# Carrier_Board.net
KiCad netlist of a schematic drawn in EAGLE
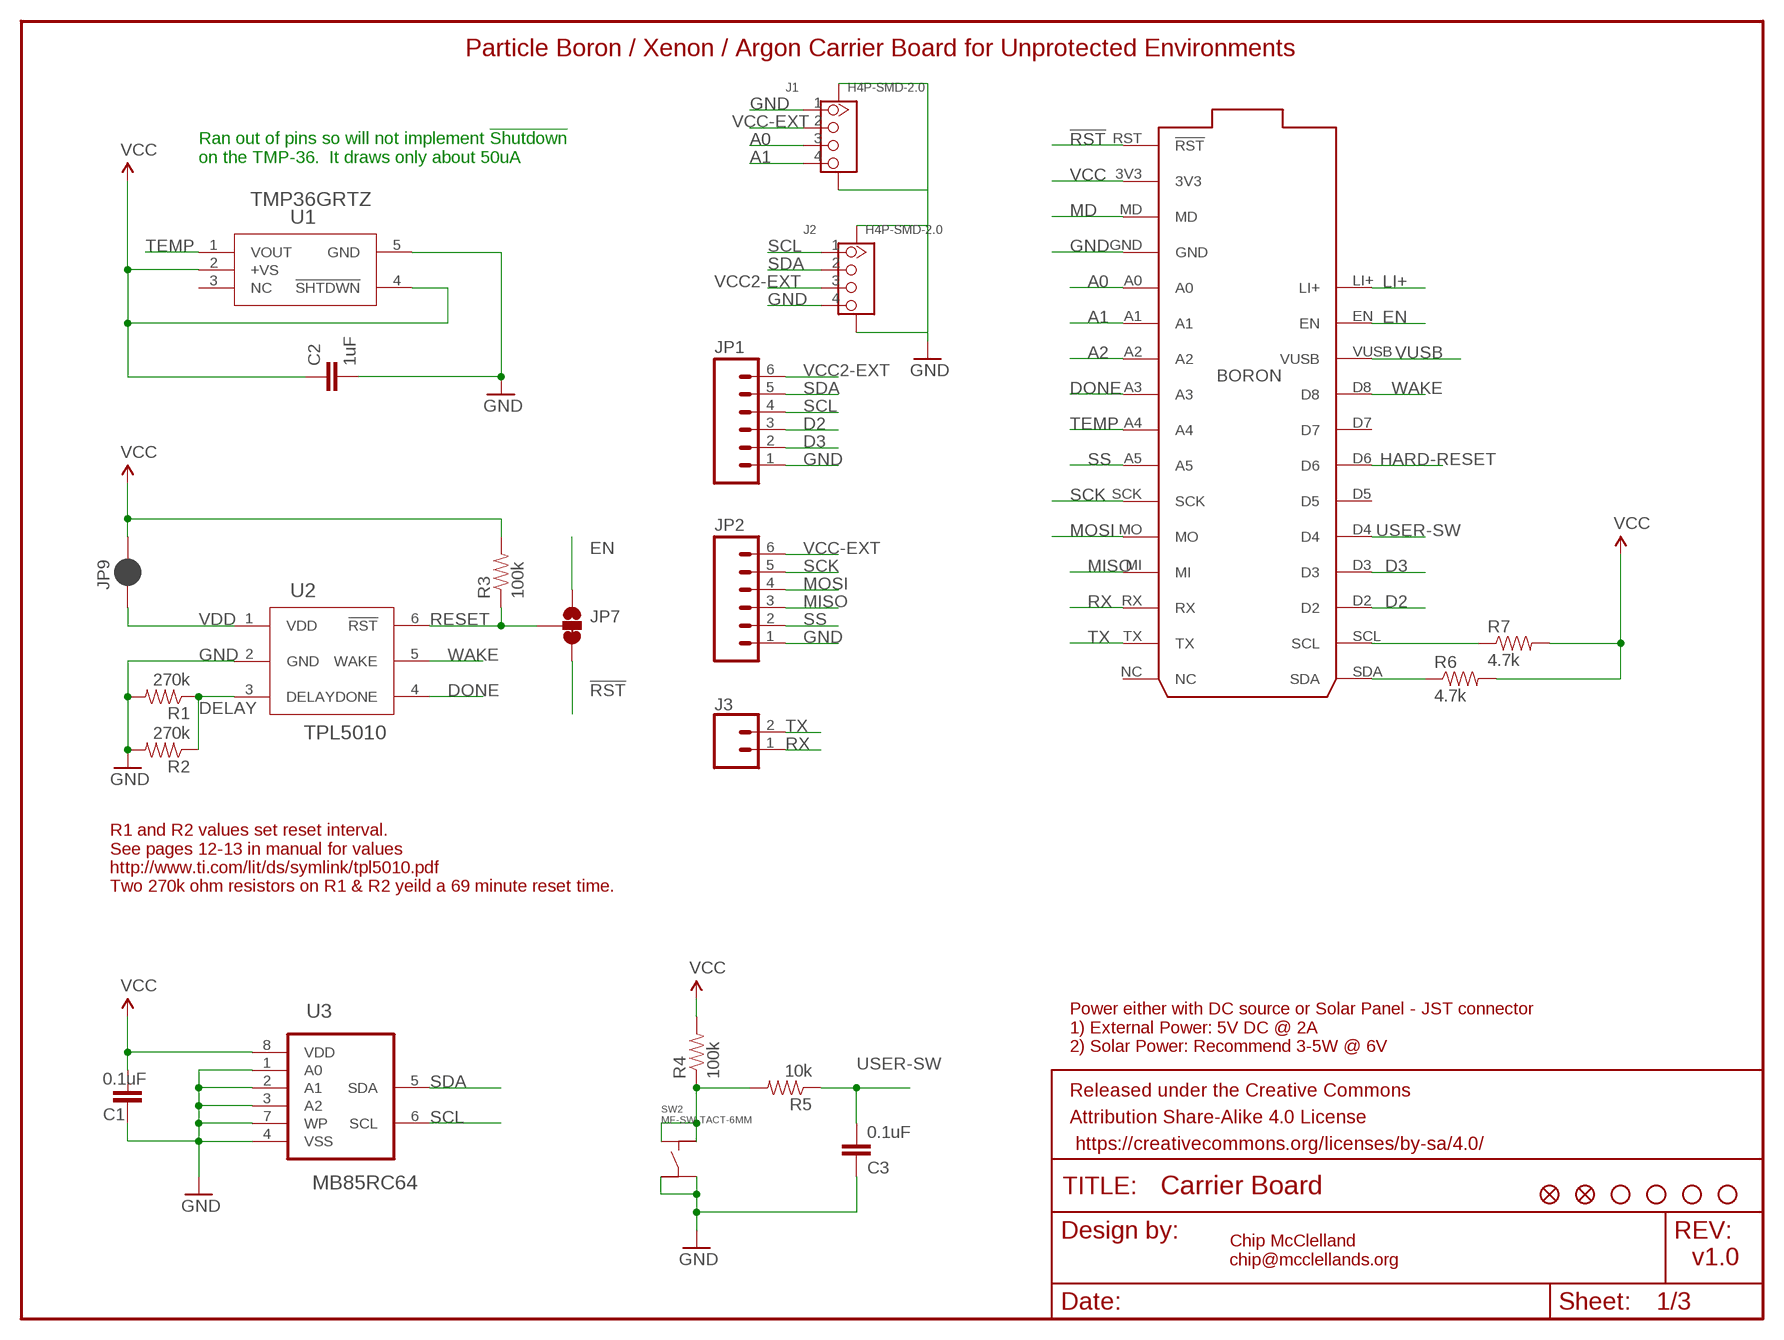
[diagram p0: schematic, sheet 1]
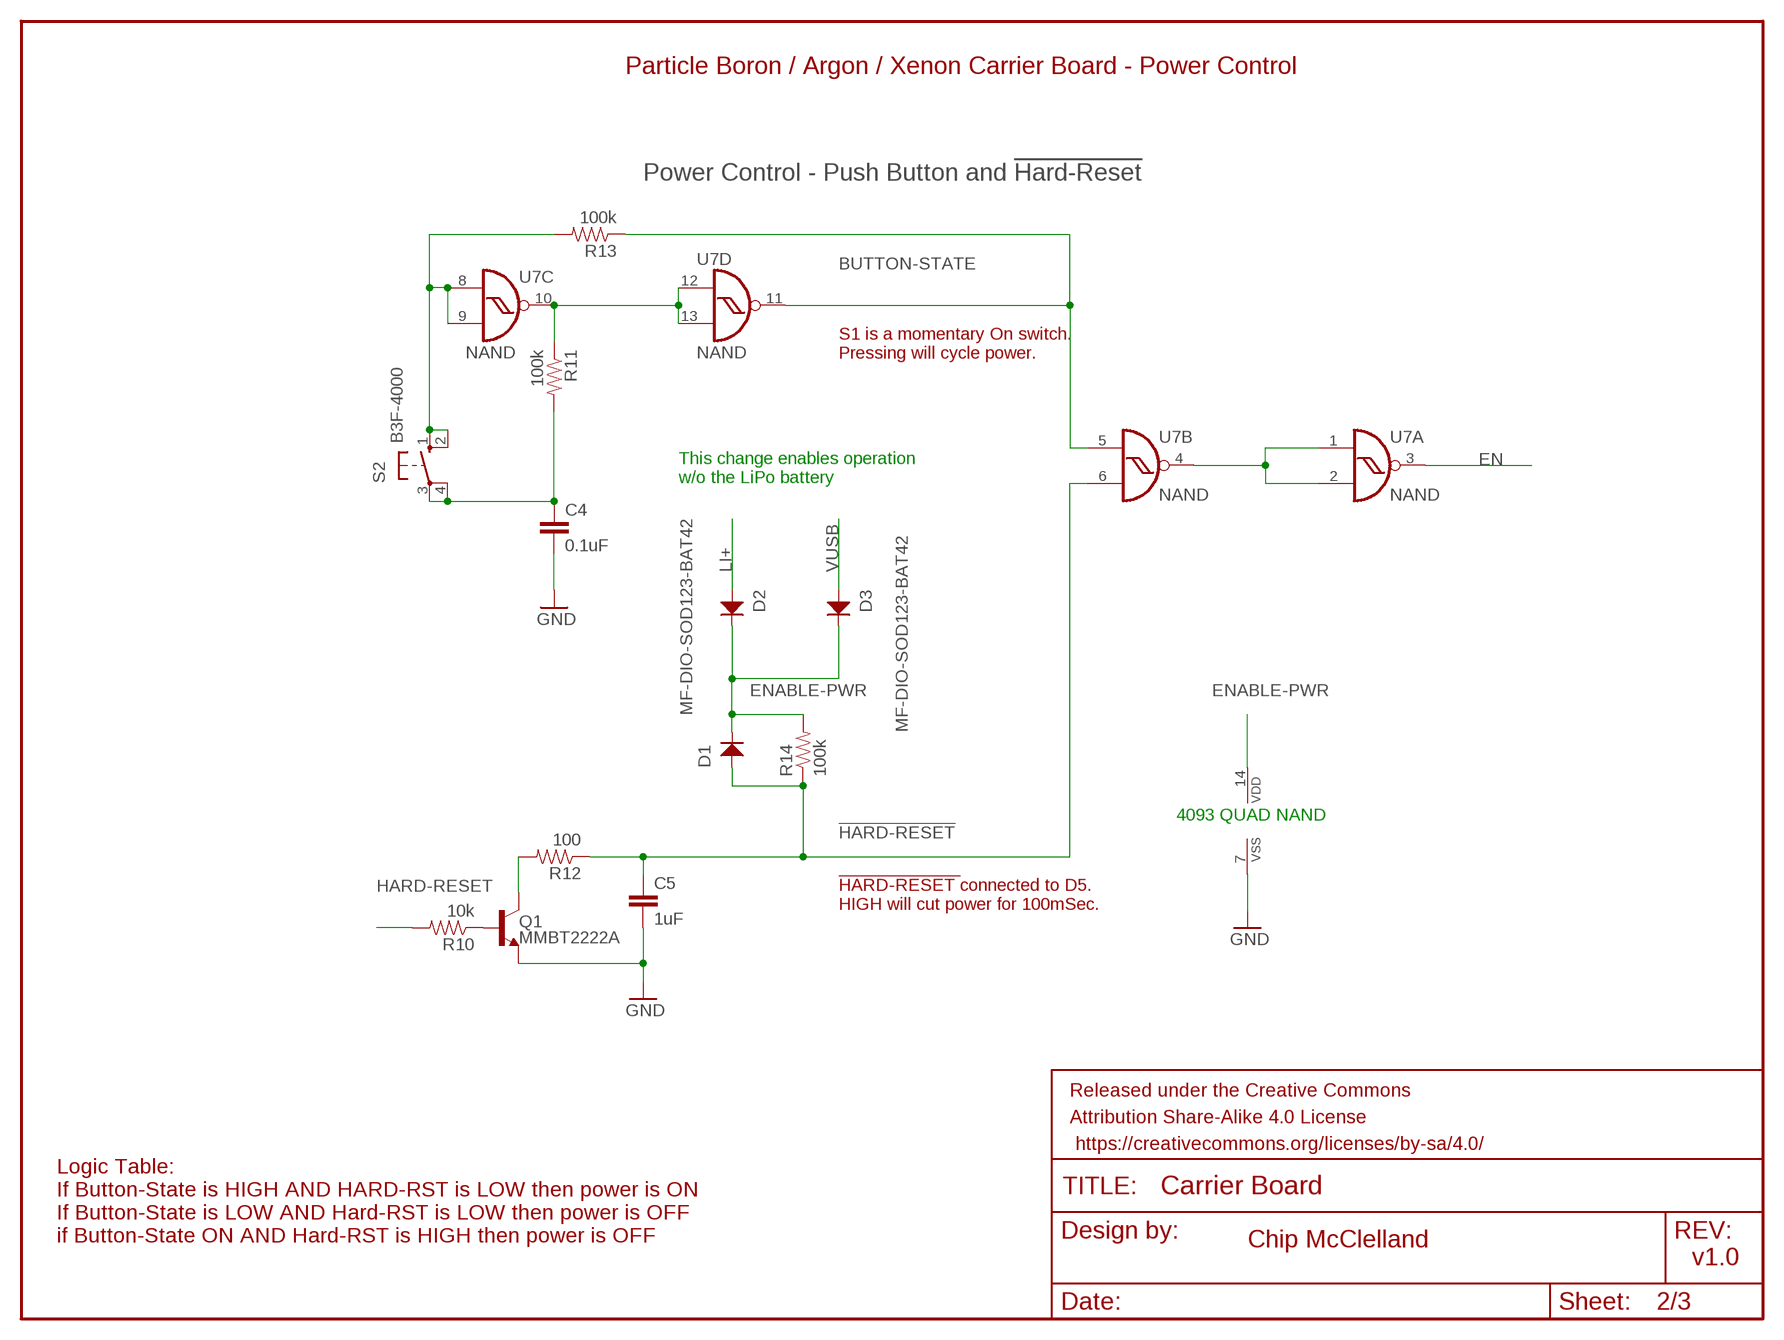
[diagram p1: schematic, sheet 2]
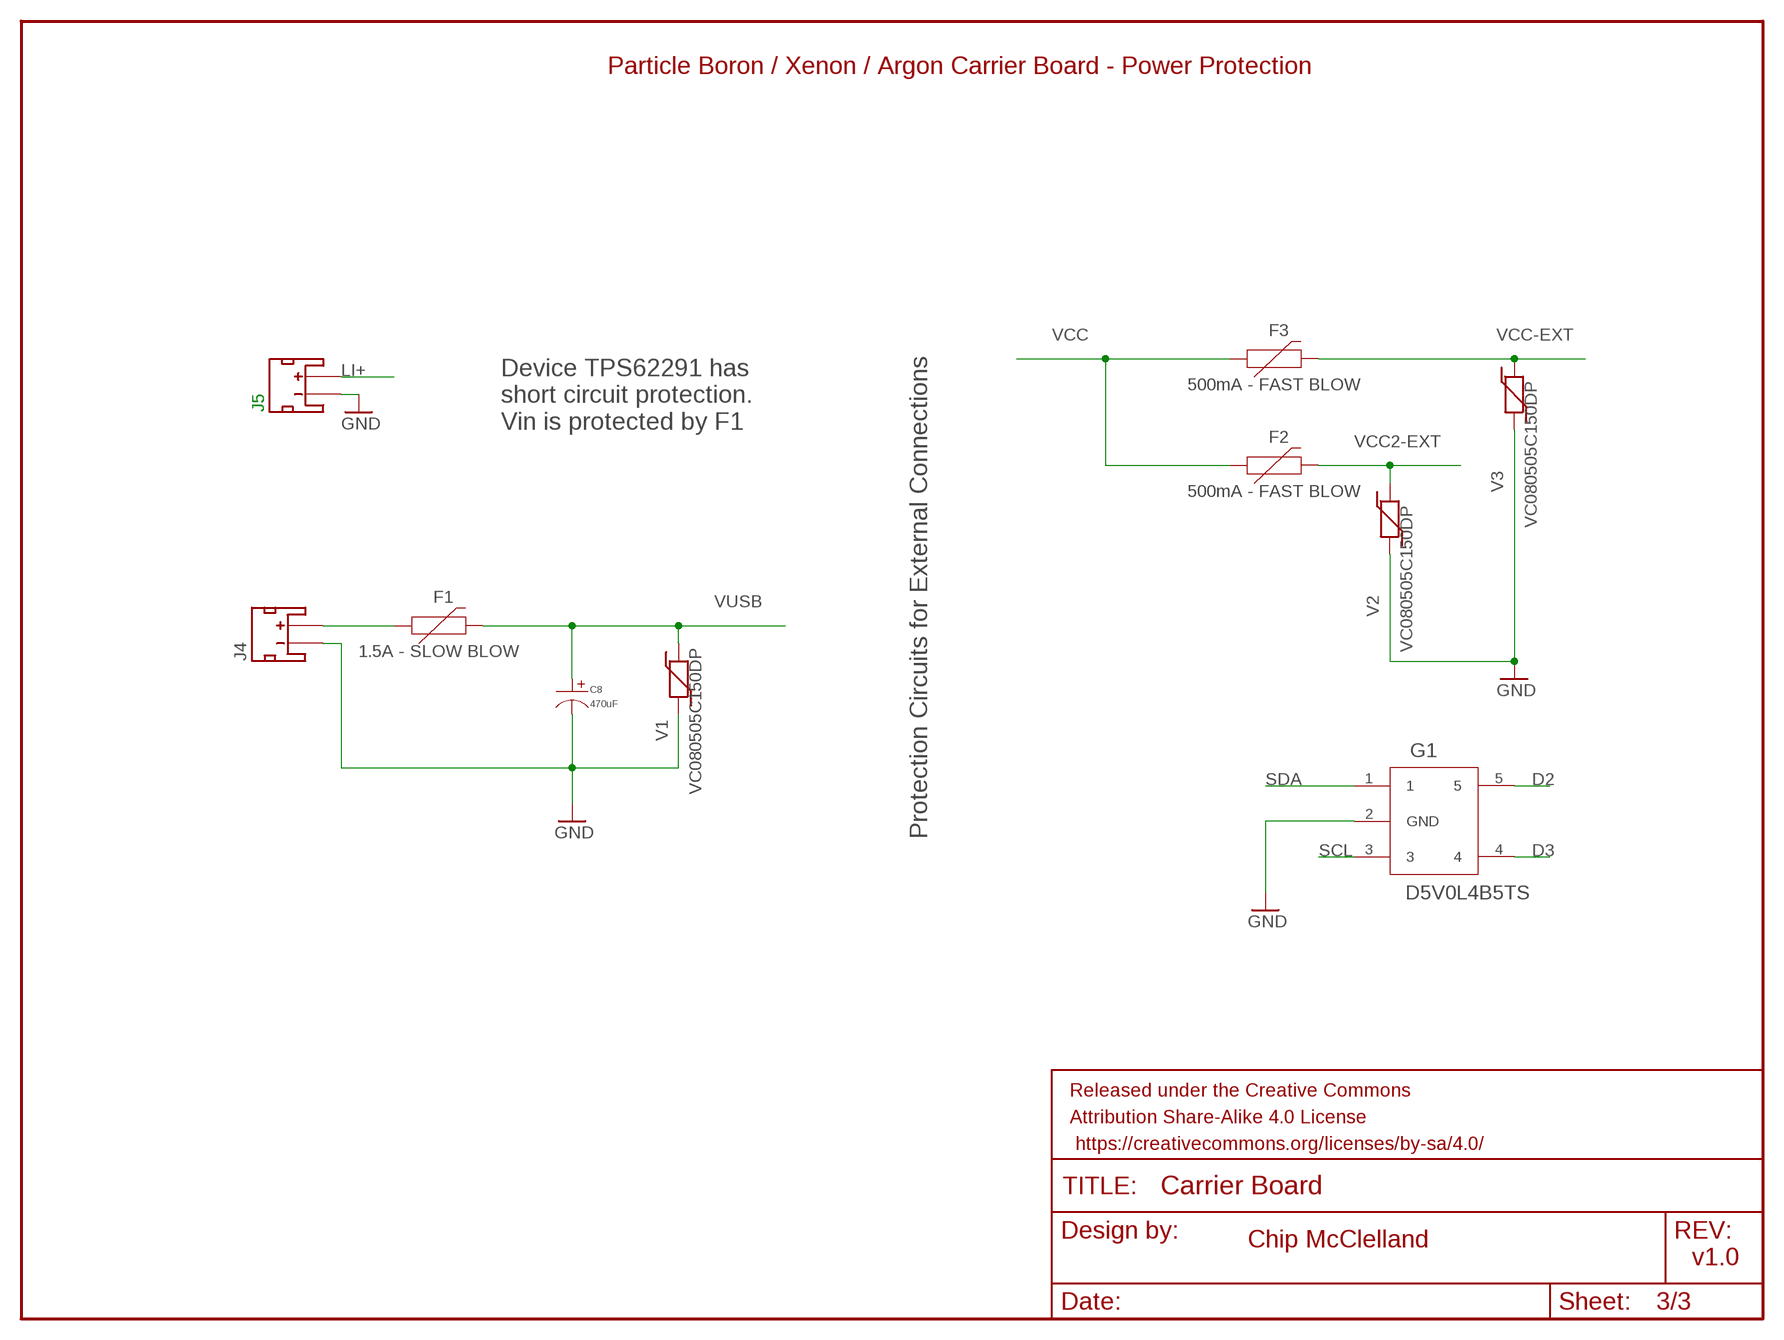
[diagram p2: schematic, sheet 3]

(export (version "E")
  (design (tool "Eeschema 10.0.6"))
  (components
    (comp (ref "C8")
      (value "470uF")
      (footprint "eagle-import:CP10MM")
      (libsource (lib "eagle-import") (part "CAPACITOR_P_10MM"))
    )
    (comp (ref "F1")
      (value "1.5A - SLOW BLOW")
      (footprint "eagle-import:1206")
      (libsource (lib "eagle-import") (part "PPTC_HALF-AMP"))
    )
    (comp (ref "F2")
      (value "500mA - FAST BLOW")
      (footprint "eagle-import:1206")
      (libsource (lib "eagle-import") (part "PPTC_HALF-AMP"))
    )
    (comp (ref "F3")
      (value "500mA - FAST BLOW")
      (footprint "eagle-import:1206")
      (libsource (lib "eagle-import") (part "PPTC_HALF-AMP"))
    )
    (comp (ref "FRAME3")
      (value "FRAME-LETTER")
      (footprint "eagle-import:CREATIVE_COMMONS")
      (libsource (lib "eagle-import") (part "FRAME-LETTER"))
    )
    (comp (ref "G1")
      (value "D5V0L4B5TS")
      (footprint "eagle-import:SOT-23-5")
      (libsource (lib "eagle-import") (part "D5V0L4B5TS"))
    )
    (comp (ref "J4")
      (value "S2B-PH-SM4-TB(LF)(SN)")
      (footprint "eagle-import:JST-2-SMD")
      (libsource (lib "eagle-import") (part "JST_2MM_MALE"))
    )
    (comp (ref "J5")
      (value "S2B-PH-SM4-TB(LF)(SN)")
      (footprint "eagle-import:JST-2-SMD")
      (libsource (lib "eagle-import") (part "JST_2MM_MALE"))
    )
    (comp (ref "V1")
      (value "VC080505C150DP")
      (footprint "eagle-import:0805")
      (libsource (lib "eagle-import") (part "VARISTOR"))
    )
    (comp (ref "V2")
      (value "VC080505C150DP")
      (footprint "eagle-import:0805")
      (libsource (lib "eagle-import") (part "VARISTOR"))
    )
    (comp (ref "V3")
      (value "VC080505C150DP")
      (footprint "eagle-import:0805")
      (libsource (lib "eagle-import") (part "VARISTOR"))
    )
    (comp (ref "BORON/ARGON/XENON")
      (value "PARTICLE-DEVICES-BORON")
      (footprint "eagle-import:PARTICLE-DEVICES_BORON")
      (libsource (lib "eagle-import") (part "PARTICLE-DEVICES-BORON"))
    )
    (comp (ref "C1")
      (value "0.1uF")
      (footprint "eagle-import:0805@1")
      (libsource (lib "eagle-import") (part "CAP0805"))
    )
    (comp (ref "C2")
      (value "1uF")
      (footprint "eagle-import:0805@1")
      (libsource (lib "eagle-import") (part "CAP0805"))
    )
    (comp (ref "C3")
      (value "0.1uF")
      (footprint "eagle-import:0805@1")
      (libsource (lib "eagle-import") (part "CAP0805"))
    )
    (comp (ref "FD1")
      (value "FIDUCIALUFIDUCIAL")
      (footprint "eagle-import:FIDUCIAL-MICRO")
      (libsource (lib "eagle-import") (part "FIDUCIALUFIDUCIAL"))
    )
    (comp (ref "FD2")
      (value "FIDUCIALUFIDUCIAL")
      (footprint "eagle-import:FIDUCIAL-MICRO")
      (libsource (lib "eagle-import") (part "FIDUCIALUFIDUCIAL"))
    )
    (comp (ref "FRAME1")
      (value "FRAME-LETTER")
      (footprint "eagle-import:CREATIVE_COMMONS")
      (libsource (lib "eagle-import") (part "FRAME-LETTER"))
    )
    (comp (ref "J1")
      (value "H4P-SMD-2.0")
      (footprint "eagle-import:HW4-SMD-2.0")
      (libsource (lib "eagle-import") (part "GROVE-CONNECTOR-SMD(4+2P-2.0)"))
    )
    (comp (ref "J2")
      (value "H4P-SMD-2.0")
      (footprint "eagle-import:HW4-SMD-2.0")
      (libsource (lib "eagle-import") (part "GROVE-CONNECTOR-SMD(4+2P-2.0)"))
    )
    (comp (ref "J3")
      (value "CONN_02")
      (footprint "eagle-import:1X02")
      (libsource (lib "eagle-import") (part "CONN_02"))
    )
    (comp (ref "JP1")
      (value "M06LOCK")
      (footprint "eagle-import:1X06_LOCK")
      (libsource (lib "eagle-import") (part "M06LOCK"))
    )
    (comp (ref "JP2")
      (value "M06LOCK")
      (footprint "eagle-import:1X06_LOCK")
      (libsource (lib "eagle-import") (part "M06LOCK"))
    )
    (comp (ref "JP3")
      (value "STAND-OFF")
      (footprint "eagle-import:STAND-OFF")
      (libsource (lib "eagle-import") (part "STAND-OFF"))
    )
    (comp (ref "JP4")
      (value "STAND-OFF")
      (footprint "eagle-import:STAND-OFF")
      (libsource (lib "eagle-import") (part "STAND-OFF"))
    )
    (comp (ref "JP5")
      (value "STAND-OFF")
      (footprint "eagle-import:STAND-OFF")
      (libsource (lib "eagle-import") (part "STAND-OFF"))
    )
    (comp (ref "JP6")
      (value "STAND-OFF")
      (footprint "eagle-import:STAND-OFF")
      (libsource (lib "eagle-import") (part "STAND-OFF"))
    )
    (comp (ref "JP7")
      (value "JUMPER-SMT_3_1-NC_TRACE_SILK")
      (footprint "eagle-import:SMT-JUMPER_3_1-NC_TRACE_SILK")
      (libsource (lib "eagle-import") (part "JUMPER-SMT_3_1-NC_TRACE_SILK"))
    )
    (comp (ref "JP9")
      (value "JUMPER-SMT_2_NC_PASTE_SILK")
      (footprint "eagle-import:SMT-JUMPER_2_NC_PASTE_SILK")
      (libsource (lib "eagle-import") (part "JUMPER-SMT_2_NC_PASTE_SILK"))
    )
    (comp (ref "R1")
      (value "270k")
      (footprint "eagle-import:0805")
      (libsource (lib "eagle-import") (part "RESISTOR0805-RES"))
    )
    (comp (ref "R2")
      (value "270k")
      (footprint "eagle-import:0805")
      (libsource (lib "eagle-import") (part "RESISTOR0805-RES"))
    )
    (comp (ref "R3")
      (value "100k")
      (footprint "eagle-import:0805")
      (libsource (lib "eagle-import") (part "RESISTOR0805-RES"))
    )
    (comp (ref "R4")
      (value "100k")
      (footprint "eagle-import:0805")
      (libsource (lib "eagle-import") (part "RESISTOR0805-RES"))
    )
    (comp (ref "R5")
      (value "10k")
      (footprint "eagle-import:0805")
      (libsource (lib "eagle-import") (part "RESISTOR0805-RES"))
    )
    (comp (ref "R6")
      (value "4.7k")
      (footprint "eagle-import:0805")
      (libsource (lib "eagle-import") (part "RESISTOR0805-RES"))
    )
    (comp (ref "R7")
      (value "4.7k")
      (footprint "eagle-import:0805")
      (libsource (lib "eagle-import") (part "RESISTOR0805-RES"))
    )
    (comp (ref "SW2")
      (value "MF-SW-TACT-6MM")
      (footprint "eagle-import:TACT6MM")
      (fields (field (name "HOUSEPART") "YES"))
      (libsource (lib "eagle-import") (part "TACT_6MM"))
    )
    (comp (ref "U1")
      (value "TMP36GRTZ")
      (footprint "eagle-import:RJ_5")
      (fields (field (name "MANUFACTURER_PART_NUMBER") "TMP36GRTZREEL7"))
      (libsource (lib "eagle-import") (part "TMP36GRTZ-REEL7"))
    )
    (comp (ref "U2")
      (value "TPL5010")
      (footprint "eagle-import:TSOT-23")
      (libsource (lib "eagle-import") (part "TPL5010"))
    )
    (comp (ref "U3")
      (value "MB85RC64")
      (footprint "eagle-import:SOIC127P600X175-8N")
      (fields (field (name "MPN") "MB85RC128PNF-G-JNE1"))
      (libsource (lib "eagle-import") (part "MB85RC128PNF-G-JNE1"))
    )
    (comp (ref "C4")
      (value "0.1uF")
      (footprint "eagle-import:0805@1")
      (libsource (lib "eagle-import") (part "CAP0805"))
    )
    (comp (ref "C5")
      (value "1uF")
      (footprint "eagle-import:0805@1")
      (libsource (lib "eagle-import") (part "CAP0805"))
    )
    (comp (ref "D1")
      (value "MF-DIO-SOD123-BAT42")
      (footprint "eagle-import:SOD-123")
      (fields (field (name "HOUSEPART") "YES"))
      (libsource (lib "eagle-import") (part "DIODES_SOD-123_BAT42"))
    )
    (comp (ref "D2")
      (value "MF-DIO-SOD123-BAT42")
      (footprint "eagle-import:SOD-123")
      (fields (field (name "HOUSEPART") "YES"))
      (libsource (lib "eagle-import") (part "DIODES_SOD-123_BAT42"))
    )
    (comp (ref "D3")
      (value "MF-DIO-SOD123-BAT42")
      (footprint "eagle-import:SOD-123")
      (fields (field (name "HOUSEPART") "YES"))
      (libsource (lib "eagle-import") (part "DIODES_SOD-123_BAT42"))
    )
    (comp (ref "FRAME2")
      (value "FRAME-LETTER")
      (footprint "eagle-import:CREATIVE_COMMONS")
      (libsource (lib "eagle-import") (part "FRAME-LETTER"))
    )
    (comp (ref "Q1")
      (value "MMBT2222A")
      (footprint "eagle-import:SOT23-3")
      (libsource (lib "eagle-import") (part "TRANS_NPN-MMBT2222AL"))
    )
    (comp (ref "R10")
      (value "10k")
      (footprint "eagle-import:0805")
      (libsource (lib "eagle-import") (part "RESISTOR0805-RES"))
    )
    (comp (ref "R11")
      (value "100k")
      (footprint "eagle-import:0805")
      (libsource (lib "eagle-import") (part "RESISTOR0805-RES"))
    )
    (comp (ref "R12")
      (value "100")
      (footprint "eagle-import:0805")
      (libsource (lib "eagle-import") (part "RESISTOR0805-RES"))
    )
    (comp (ref "R13")
      (value "100k")
      (footprint "eagle-import:0805")
      (libsource (lib "eagle-import") (part "RESISTOR0805-RES"))
    )
    (comp (ref "R14")
      (value "100k")
      (footprint "eagle-import:0805")
      (libsource (lib "eagle-import") (part "RESISTOR0805-RES"))
    )
    (comp (ref "S2")
      (value "B3F-4000")
      (footprint "eagle-import:B3F-40XX-ROUND")
      (libsource (lib "eagle-import") (part "40-XX-ROUND"))
    )
    (comp (ref "U7")
      (value "NAND")
      (footprint "eagle-import:MC14093B-TSSOP14")
      (libsource (lib "eagle-import") (part "4093DT"))
    )
  )
  (nets
    (net (code "1") (name "A0") (class "Default")
      (node (ref "BORON/ARGON/XENON") (pin "A0") (pinfunction "A0_A0") (pintype "bidirectional"))
      (node (ref "J1") (pin "3") (pinfunction "3_3") (pintype "bidirectional"))
    )
    (net (code "2") (name "A1") (class "Default")
      (node (ref "BORON/ARGON/XENON") (pin "A1") (pinfunction "A1_A1") (pintype "bidirectional"))
      (node (ref "J1") (pin "4") (pinfunction "4_4") (pintype "bidirectional"))
    )
    (net (code "3") (name "A2") (class "Default")
      (node (ref "BORON/ARGON/XENON") (pin "A2") (pinfunction "A2_A2") (pintype "bidirectional"))
    )
    (net (code "4") (name "BUTTON-STATE") (class "Default")
      (node (ref "R13") (pin "1") (pinfunction "1_1") (pintype "passive"))
      (node (ref "U7") (pin "11") (pinfunction "O_11") (pintype "output"))
      (node (ref "U7") (pin "5") (pinfunction "I0_5") (pintype "input"))
    )
    (net (code "5") (name "D2") (class "Default")
      (node (ref "BORON/ARGON/XENON") (pin "D2") (pinfunction "D2_D2") (pintype "bidirectional"))
      (node (ref "G1") (pin "5") (pinfunction "5_5") (pintype "output"))
      (node (ref "JP1") (pin "3") (pinfunction "3_3") (pintype "passive"))
    )
    (net (code "6") (name "D3") (class "Default")
      (node (ref "BORON/ARGON/XENON") (pin "D3") (pinfunction "D3_D3") (pintype "bidirectional"))
      (node (ref "G1") (pin "4") (pinfunction "4_4") (pintype "output"))
      (node (ref "JP1") (pin "2") (pinfunction "2_2") (pintype "passive"))
    )
    (net (code "7") (name "DELAY") (class "Default")
      (node (ref "R1") (pin "1") (pinfunction "1_1") (pintype "passive"))
      (node (ref "R2") (pin "1") (pinfunction "1_1") (pintype "passive"))
      (node (ref "U2") (pin "3") (pinfunction "DELAY_3") (pintype "input"))
    )
    (net (code "8") (name "DONE") (class "Default")
      (node (ref "BORON/ARGON/XENON") (pin "A3") (pinfunction "A3_A3") (pintype "bidirectional"))
      (node (ref "U2") (pin "4") (pinfunction "DONE_4") (pintype "input"))
    )
    (net (code "9") (name "EN") (class "Default")
      (node (ref "BORON/ARGON/XENON") (pin "EN") (pinfunction "EN_EN") (pintype "bidirectional"))
      (node (ref "JP7") (pin "1") (pinfunction "1_1") (pintype "passive"))
      (node (ref "U7") (pin "3") (pinfunction "O_3") (pintype "output"))
    )
    (net (code "10") (name "ENABLE-PWR") (class "Default")
      (node (ref "D1") (pin "CATHODE") (pinfunction "CATHODE_CATHODE") (pintype "bidirectional"))
      (node (ref "D2") (pin "CATHODE") (pinfunction "CATHODE_CATHODE") (pintype "bidirectional"))
      (node (ref "D3") (pin "CATHODE") (pinfunction "CATHODE_CATHODE") (pintype "bidirectional"))
      (node (ref "R14") (pin "2") (pinfunction "2_2") (pintype "passive"))
      (node (ref "U7") (pin "14") (pinfunction "VDD_14") (pintype "power_in"))
    )
    (net (code "11") (name "GND") (class "Default")
      (node (ref "BORON/ARGON/XENON") (pin "GND") (pinfunction "GND_GND") (pintype "bidirectional"))
      (node (ref "C1") (pin "2") (pinfunction "2_2") (pintype "passive"))
      (node (ref "C2") (pin "2") (pinfunction "2_2") (pintype "passive"))
      (node (ref "C3") (pin "2") (pinfunction "2_2") (pintype "passive"))
      (node (ref "C4") (pin "2") (pinfunction "2_2") (pintype "passive"))
      (node (ref "C5") (pin "2") (pinfunction "2_2") (pintype "passive"))
      (node (ref "C8") (pin "P$2") (pinfunction "P$2_P$2") (pintype "passive"))
      (node (ref "G1") (pin "2") (pinfunction "GND_2") (pintype "power_in"))
      (node (ref "J1") (pin "1") (pinfunction "1_1") (pintype "bidirectional"))
      (node (ref "J1") (pin "SS1") (pinfunction "SS1_SS1") (pintype "bidirectional"))
      (node (ref "J1") (pin "SS2") (pinfunction "SS2_SS2") (pintype "bidirectional"))
      (node (ref "J2") (pin "4") (pinfunction "4_4") (pintype "bidirectional"))
      (node (ref "J2") (pin "SS1") (pinfunction "SS1_SS1") (pintype "bidirectional"))
      (node (ref "J2") (pin "SS2") (pinfunction "SS2_SS2") (pintype "bidirectional"))
      (node (ref "J4") (pin "1") (pinfunction "-_1") (pintype "bidirectional"))
      (node (ref "J5") (pin "1") (pinfunction "-_1") (pintype "bidirectional"))
      (node (ref "JP1") (pin "1") (pinfunction "1_1") (pintype "passive"))
      (node (ref "JP2") (pin "1") (pinfunction "1_1") (pintype "passive"))
      (node (ref "Q1") (pin "2") (pinfunction "E_2") (pintype "passive"))
      (node (ref "R1") (pin "2") (pinfunction "2_2") (pintype "passive"))
      (node (ref "R2") (pin "2") (pinfunction "2_2") (pintype "passive"))
      (node (ref "SW2") (pin "P$3") (pinfunction "P$3_P$3") (pintype "bidirectional"))
      (node (ref "SW2") (pin "P$4") (pinfunction "P$4_P$4") (pintype "bidirectional"))
      (node (ref "U1") (pin "5") (pinfunction "GND_5") (pintype "passive"))
      (node (ref "U2") (pin "2") (pinfunction "GND_2") (pintype "power_in"))
      (node (ref "U3") (pin "1") (pinfunction "A0_1") (pintype "input"))
      (node (ref "U3") (pin "2") (pinfunction "A1_2") (pintype "input"))
      (node (ref "U3") (pin "3") (pinfunction "A2_3") (pintype "input"))
      (node (ref "U3") (pin "4") (pinfunction "VSS_4") (pintype "passive"))
      (node (ref "U3") (pin "7") (pinfunction "WP_7") (pintype "input"))
      (node (ref "U7") (pin "7") (pinfunction "VSS_7") (pintype "power_in"))
      (node (ref "V1") (pin "1") (pinfunction "1_1") (pintype "passive"))
      (node (ref "V2") (pin "1") (pinfunction "1_1") (pintype "passive"))
      (node (ref "V3") (pin "1") (pinfunction "1_1") (pintype "passive"))
    )
    (net (code "12") (name "HARD-RESET") (class "Default")
      (node (ref "BORON/ARGON/XENON") (pin "D6") (pinfunction "D6_D6") (pintype "bidirectional"))
      (node (ref "R10") (pin "2") (pinfunction "2_2") (pintype "passive"))
    )
    (net (code "13") (name "LI+") (class "Default")
      (node (ref "BORON/ARGON/XENON") (pin "LI+") (pinfunction "LI+_LI+") (pintype "bidirectional"))
      (node (ref "D2") (pin "ANODE") (pinfunction "ANODE_ANODE") (pintype "bidirectional"))
      (node (ref "J5") (pin "2") (pinfunction "+_2") (pintype "bidirectional"))
    )
    (net (code "14") (name "MD") (class "Default")
      (node (ref "BORON/ARGON/XENON") (pin "MD") (pinfunction "MD_MD") (pintype "bidirectional"))
    )
    (net (code "15") (name "MISO") (class "Default")
      (node (ref "BORON/ARGON/XENON") (pin "MI") (pinfunction "MI_MI") (pintype "bidirectional"))
      (node (ref "JP2") (pin "3") (pinfunction "3_3") (pintype "passive"))
    )
    (net (code "16") (name "MOSI") (class "Default")
      (node (ref "BORON/ARGON/XENON") (pin "MO") (pinfunction "MO_MO") (pintype "bidirectional"))
      (node (ref "JP2") (pin "4") (pinfunction "4_4") (pintype "passive"))
    )
    (net (code "17") (name "Net-(J4-+)") (class "Default")
      (node (ref "F1") (pin "1") (pinfunction "1_1") (pintype "bidirectional"))
      (node (ref "J4") (pin "2") (pinfunction "+_2") (pintype "bidirectional"))
    )
    (net (code "18") (name "Net-(Q1-B)") (class "Default")
      (node (ref "Q1") (pin "1") (pinfunction "B_1") (pintype "passive"))
      (node (ref "R10") (pin "1") (pinfunction "1_1") (pintype "passive"))
    )
    (net (code "19") (name "Net-(Q1-C)") (class "Default")
      (node (ref "Q1") (pin "3") (pinfunction "C_3") (pintype "passive"))
      (node (ref "R12") (pin "2") (pinfunction "2_2") (pintype "passive"))
    )
    (net (code "20") (name "Net-(R4-Pad1)") (class "Default")
      (node (ref "R4") (pin "1") (pinfunction "1_1") (pintype "passive"))
      (node (ref "R5") (pin "2") (pinfunction "2_2") (pintype "passive"))
      (node (ref "SW2") (pin "P$1") (pinfunction "P$1_P$1") (pintype "bidirectional"))
      (node (ref "SW2") (pin "P$2") (pinfunction "P$2_P$2") (pintype "bidirectional"))
    )
    (net (code "21") (name "Net-(S2-P)") (class "Default")
      (node (ref "C4") (pin "1") (pinfunction "1_1") (pintype "passive"))
      (node (ref "R11") (pin "2") (pinfunction "2_2") (pintype "passive"))
      (node (ref "S2") (pin "3") (pinfunction "P_3") (pintype "passive"))
      (node (ref "S2") (pin "4") (pinfunction "P1_4") (pintype "passive"))
    )
    (net (code "22") (name "Net-(S2-S)") (class "Default")
      (node (ref "R13") (pin "2") (pinfunction "2_2") (pintype "passive"))
      (node (ref "S2") (pin "1") (pinfunction "S_1") (pintype "passive"))
      (node (ref "S2") (pin "2") (pinfunction "S1_2") (pintype "passive"))
      (node (ref "U7") (pin "8") (pinfunction "I0_8") (pintype "input"))
      (node (ref "U7") (pin "9") (pinfunction "I1_9") (pintype "input"))
    )
    (net (code "23") (name "Net-(U7A-I0)") (class "Default")
      (node (ref "U7") (pin "1") (pinfunction "I0_1") (pintype "input"))
      (node (ref "U7") (pin "2") (pinfunction "I1_2") (pintype "input"))
      (node (ref "U7") (pin "4") (pinfunction "O_4") (pintype "output"))
    )
    (net (code "24") (name "Net-(U7C-O)") (class "Default")
      (node (ref "R11") (pin "1") (pinfunction "1_1") (pintype "passive"))
      (node (ref "U7") (pin "10") (pinfunction "O_10") (pintype "output"))
      (node (ref "U7") (pin "12") (pinfunction "I0_12") (pintype "input"))
      (node (ref "U7") (pin "13") (pinfunction "I1_13") (pintype "input"))
    )
    (net (code "25") (name "RESET") (class "Default")
      (node (ref "JP7") (pin "2") (pinfunction "2_2") (pintype "passive"))
      (node (ref "R3") (pin "1") (pinfunction "1_1") (pintype "passive"))
      (node (ref "U2") (pin "6") (pinfunction "~{RST}_6") (pintype "bidirectional"))
    )
    (net (code "26") (name "RX") (class "Default")
      (node (ref "BORON/ARGON/XENON") (pin "RX") (pinfunction "RX_RX") (pintype "bidirectional"))
      (node (ref "J3") (pin "1") (pinfunction "1_1") (pintype "passive"))
    )
    (net (code "27") (name "SCK") (class "Default")
      (node (ref "BORON/ARGON/XENON") (pin "SCK") (pinfunction "SCK_SCK") (pintype "bidirectional"))
      (node (ref "JP2") (pin "5") (pinfunction "5_5") (pintype "passive"))
    )
    (net (code "28") (name "SCL") (class "Default")
      (node (ref "BORON/ARGON/XENON") (pin "SCL") (pinfunction "SCL_SCL") (pintype "bidirectional"))
      (node (ref "G1") (pin "3") (pinfunction "3_3") (pintype "input"))
      (node (ref "J2") (pin "1") (pinfunction "1_1") (pintype "bidirectional"))
      (node (ref "JP1") (pin "4") (pinfunction "4_4") (pintype "passive"))
      (node (ref "R7") (pin "1") (pinfunction "1_1") (pintype "passive"))
      (node (ref "U3") (pin "6") (pinfunction "SCL_6") (pintype "input"))
    )
    (net (code "29") (name "SDA") (class "Default")
      (node (ref "BORON/ARGON/XENON") (pin "SDA") (pinfunction "SDA_SDA") (pintype "bidirectional"))
      (node (ref "G1") (pin "1") (pinfunction "1_1") (pintype "input"))
      (node (ref "J2") (pin "2") (pinfunction "2_2") (pintype "bidirectional"))
      (node (ref "JP1") (pin "5") (pinfunction "5_5") (pintype "passive"))
      (node (ref "R6") (pin "1") (pinfunction "1_1") (pintype "passive"))
      (node (ref "U3") (pin "5") (pinfunction "SDA_5") (pintype "bidirectional"))
    )
    (net (code "30") (name "SS") (class "Default")
      (node (ref "BORON/ARGON/XENON") (pin "A5") (pinfunction "A5_A5") (pintype "bidirectional"))
      (node (ref "JP2") (pin "2") (pinfunction "2_2") (pintype "passive"))
    )
    (net (code "31") (name "TEMP") (class "Default")
      (node (ref "BORON/ARGON/XENON") (pin "A4") (pinfunction "A4_A4") (pintype "bidirectional"))
      (node (ref "U1") (pin "1") (pinfunction "VOUT_1") (pintype "passive"))
    )
    (net (code "32") (name "TX") (class "Default")
      (node (ref "BORON/ARGON/XENON") (pin "TX") (pinfunction "TX_TX") (pintype "bidirectional"))
      (node (ref "J3") (pin "2") (pinfunction "2_2") (pintype "passive"))
    )
    (net (code "33") (name "USER-SW") (class "Default")
      (node (ref "BORON/ARGON/XENON") (pin "D4") (pinfunction "D4_D4") (pintype "bidirectional"))
      (node (ref "C3") (pin "1") (pinfunction "1_1") (pintype "passive"))
      (node (ref "R5") (pin "1") (pinfunction "1_1") (pintype "passive"))
    )
    (net (code "34") (name "VCC") (class "Default")
      (node (ref "BORON/ARGON/XENON") (pin "3V3") (pinfunction "3V3_3V3") (pintype "bidirectional"))
      (node (ref "C1") (pin "1") (pinfunction "1_1") (pintype "passive"))
      (node (ref "C2") (pin "1") (pinfunction "1_1") (pintype "passive"))
      (node (ref "F2") (pin "1") (pinfunction "1_1") (pintype "bidirectional"))
      (node (ref "F3") (pin "1") (pinfunction "1_1") (pintype "bidirectional"))
      (node (ref "JP9") (pin "2") (pinfunction "2_2") (pintype "passive"))
      (node (ref "R3") (pin "2") (pinfunction "2_2") (pintype "passive"))
      (node (ref "R4") (pin "2") (pinfunction "2_2") (pintype "passive"))
      (node (ref "R6") (pin "2") (pinfunction "2_2") (pintype "passive"))
      (node (ref "R7") (pin "2") (pinfunction "2_2") (pintype "passive"))
      (node (ref "U1") (pin "2") (pinfunction "+VS_2") (pintype "power_in"))
      (node (ref "U1") (pin "4") (pinfunction "~{SHTDWN}_4") (pintype "passive"))
      (node (ref "U3") (pin "8") (pinfunction "VDD_8") (pintype "power_in"))
    )
    (net (code "35") (name "VCC-EXT") (class "Default")
      (node (ref "F3") (pin "2") (pinfunction "2_2") (pintype "bidirectional"))
      (node (ref "J1") (pin "2") (pinfunction "2_2") (pintype "bidirectional"))
      (node (ref "JP2") (pin "6") (pinfunction "6_6") (pintype "passive"))
      (node (ref "V3") (pin "2") (pinfunction "2_2") (pintype "passive"))
    )
    (net (code "36") (name "VCC2-EXT") (class "Default")
      (node (ref "F2") (pin "2") (pinfunction "2_2") (pintype "bidirectional"))
      (node (ref "J2") (pin "3") (pinfunction "3_3") (pintype "bidirectional"))
      (node (ref "JP1") (pin "6") (pinfunction "6_6") (pintype "passive"))
      (node (ref "V2") (pin "2") (pinfunction "2_2") (pintype "passive"))
    )
    (net (code "37") (name "VDD") (class "Default")
      (node (ref "JP9") (pin "1") (pinfunction "1_1") (pintype "passive"))
      (node (ref "U2") (pin "1") (pinfunction "VDD_1") (pintype "power_in"))
    )
    (net (code "38") (name "VUSB") (class "Default")
      (node (ref "BORON/ARGON/XENON") (pin "VUSB") (pinfunction "VUSB_VUSB") (pintype "bidirectional"))
      (node (ref "C8") (pin "P$1") (pinfunction "P$1_P$1") (pintype "passive"))
      (node (ref "D3") (pin "ANODE") (pinfunction "ANODE_ANODE") (pintype "bidirectional"))
      (node (ref "F1") (pin "2") (pinfunction "2_2") (pintype "bidirectional"))
      (node (ref "V1") (pin "2") (pinfunction "2_2") (pintype "passive"))
    )
    (net (code "39") (name "WAKE") (class "Default")
      (node (ref "BORON/ARGON/XENON") (pin "D8") (pinfunction "D8_D8") (pintype "bidirectional"))
      (node (ref "U2") (pin "5") (pinfunction "WAKE_5") (pintype "bidirectional"))
    )
    (net (code "40") (name "unconnected-(BORON/ARGON/XENON-PadD5)") (class "Default")
      (node (ref "BORON/ARGON/XENON") (pin "D5") (pinfunction "D5_D5") (pintype "bidirectional"))
    )
    (net (code "41") (name "unconnected-(BORON/ARGON/XENON-PadD7)") (class "Default")
      (node (ref "BORON/ARGON/XENON") (pin "D7") (pinfunction "D7_D7") (pintype "bidirectional"))
    )
    (net (code "42") (name "unconnected-(BORON/ARGON/XENON-PadNC)") (class "Default")
      (node (ref "BORON/ARGON/XENON") (pin "NC") (pinfunction "NC_NC") (pintype "bidirectional"))
    )
    (net (code "43") (name "unconnected-(J4-PAD1-PadNC1)") (class "Default")
      (node (ref "J4") (pin "NC1") (pinfunction "PAD1_NC1") (pintype "bidirectional"))
    )
    (net (code "44") (name "unconnected-(J4-PAD2-PadNC2)") (class "Default")
      (node (ref "J4") (pin "NC2") (pinfunction "PAD2_NC2") (pintype "bidirectional"))
    )
    (net (code "45") (name "unconnected-(J5-PAD1-PadNC1)") (class "Default")
      (node (ref "J5") (pin "NC1") (pinfunction "PAD1_NC1") (pintype "bidirectional"))
    )
    (net (code "46") (name "unconnected-(J5-PAD2-PadNC2)") (class "Default")
      (node (ref "J5") (pin "NC2") (pinfunction "PAD2_NC2") (pintype "bidirectional"))
    )
    (net (code "47") (name "unconnected-(U1-NC-Pad3)") (class "Default")
      (node (ref "U1") (pin "3") (pinfunction "NC_3") (pintype "passive"))
    )
    (net (code "48") (name "~{HARD-RESET}") (class "Default")
      (node (ref "C5") (pin "1") (pinfunction "1_1") (pintype "passive"))
      (node (ref "D1") (pin "ANODE") (pinfunction "ANODE_ANODE") (pintype "bidirectional"))
      (node (ref "R12") (pin "1") (pinfunction "1_1") (pintype "passive"))
      (node (ref "R14") (pin "1") (pinfunction "1_1") (pintype "passive"))
      (node (ref "U7") (pin "6") (pinfunction "I1_6") (pintype "input"))
    )
    (net (code "49") (name "~{RST}") (class "Default")
      (node (ref "BORON/ARGON/XENON") (pin "RST") (pinfunction "~{RST}_RST") (pintype "bidirectional"))
      (node (ref "JP7") (pin "3") (pinfunction "3_3") (pintype "passive"))
    )
  )
)
